# buck_boost.net
KiCad netlist of a schematic drawn in Altium Designer
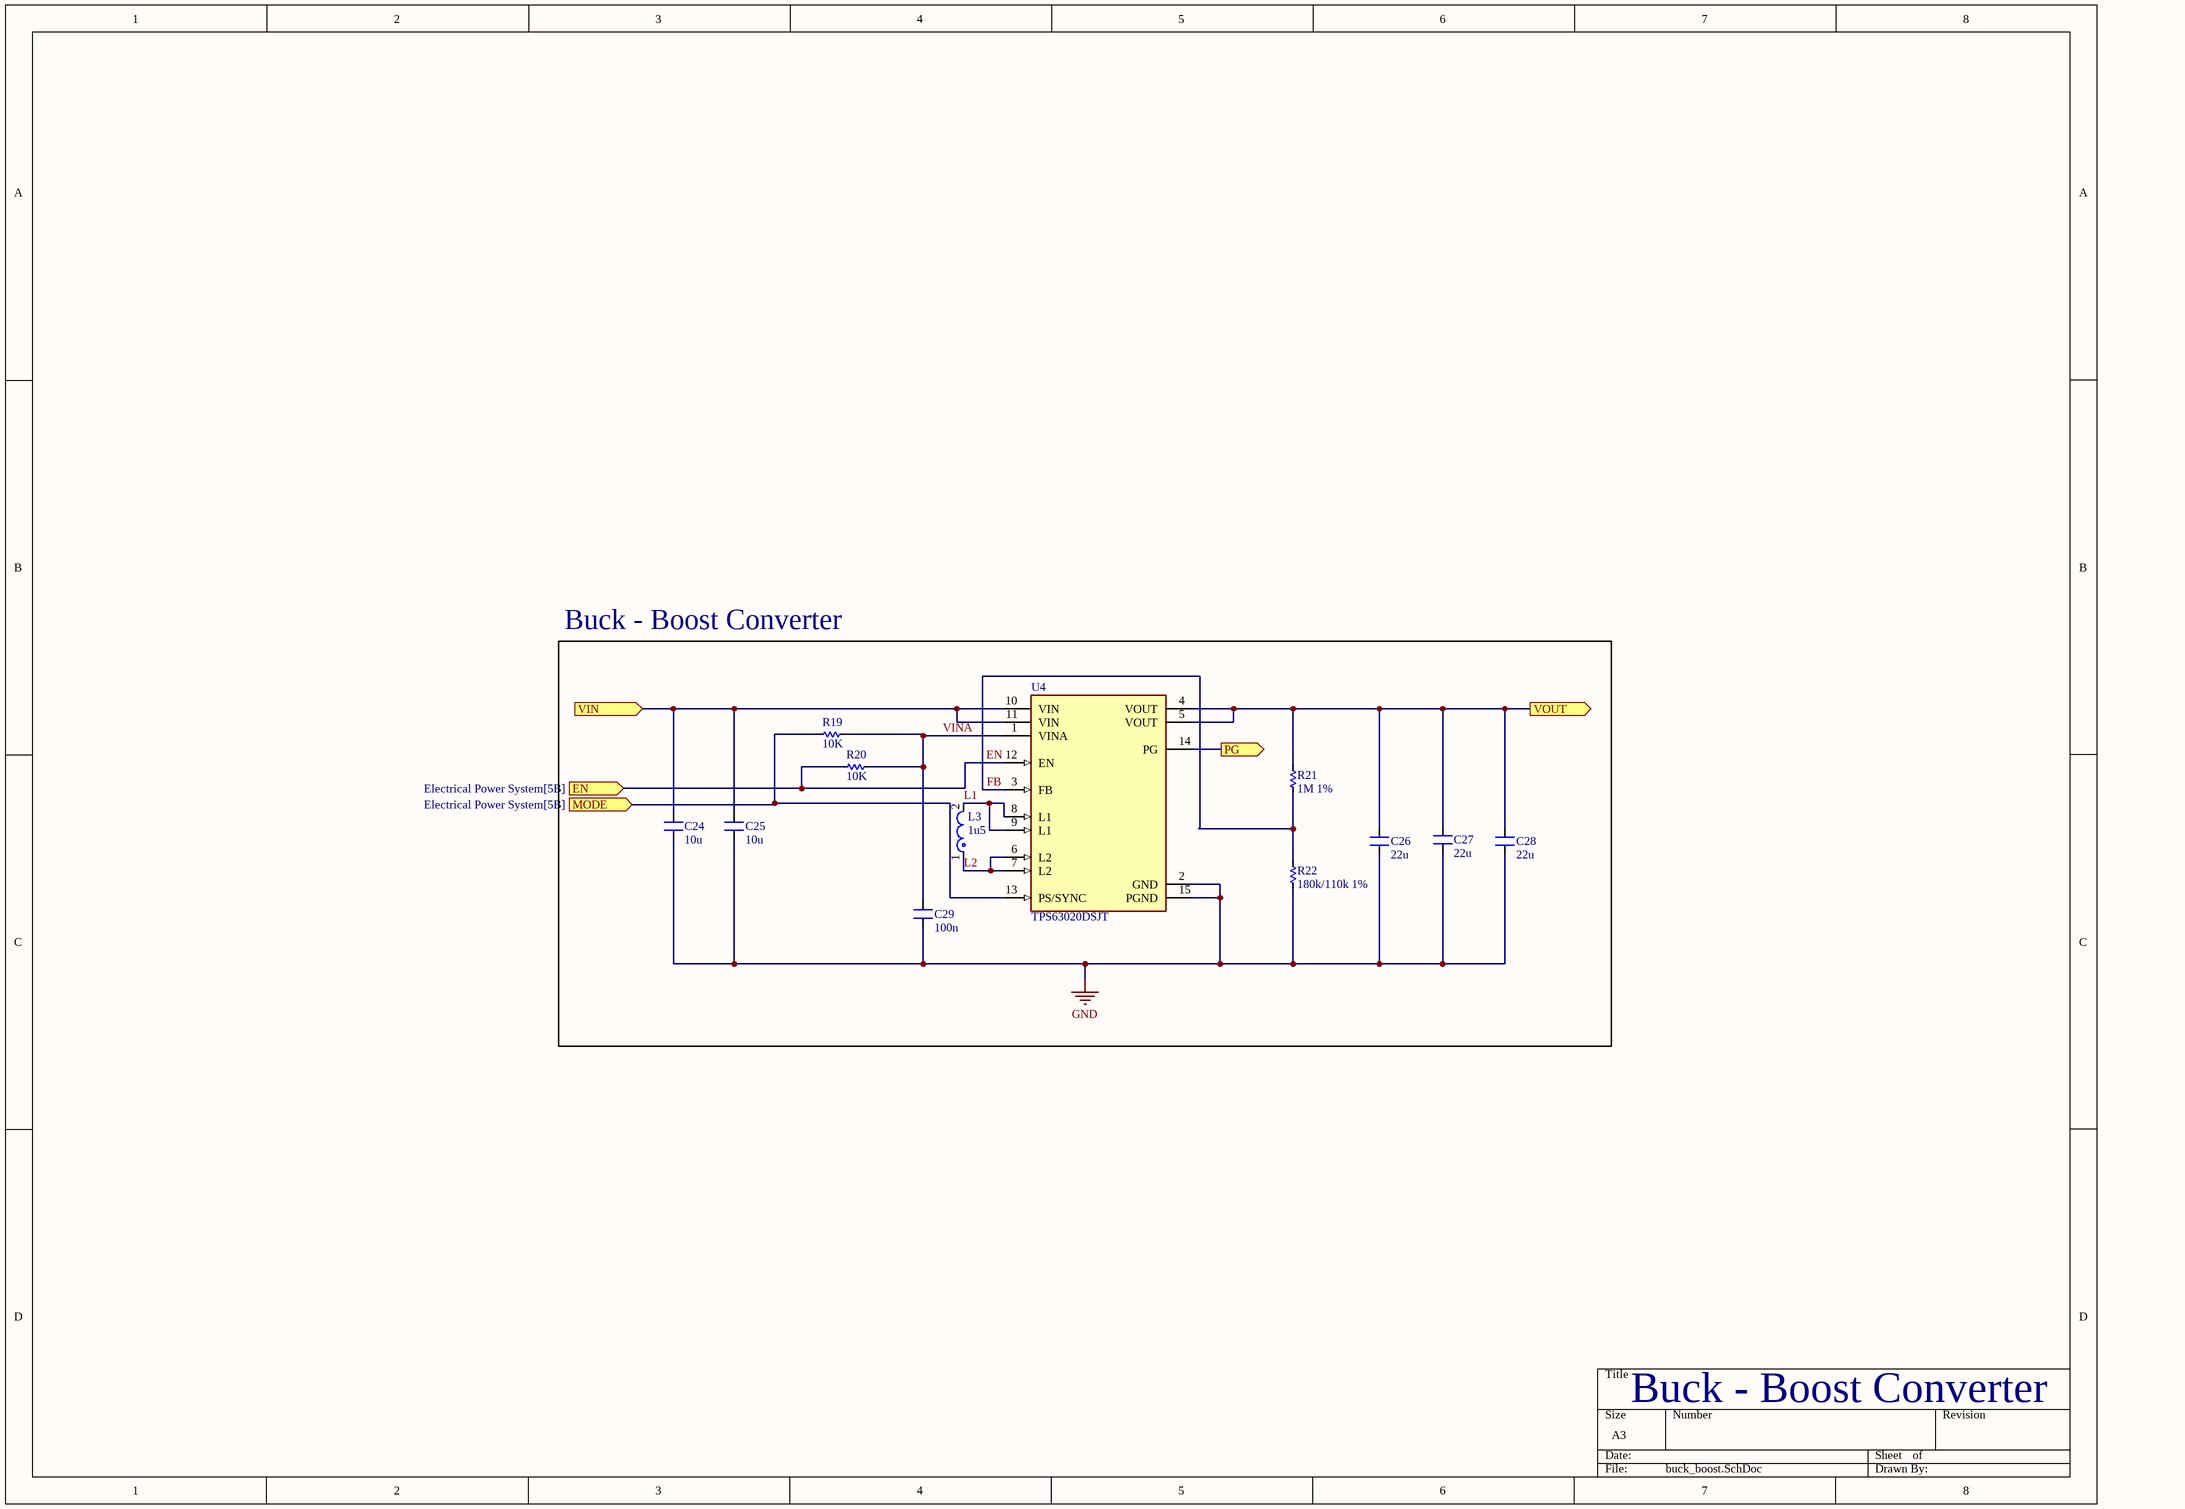
[diagram p0: buck_boost.SchDoc]

(export (version "E")
  (design (tool "Eeschema 10.0.6"))
  (components
    (comp (ref "C24")
      (value "10u")
      (footprint "CN-SMD-0603")
      (libsource (lib "Sang_library") (part "Capacitors"))
    )
    (comp (ref "C25")
      (value "10u")
      (footprint "CN-SMD-0603")
      (libsource (lib "Sang_library") (part "Capacitors"))
    )
    (comp (ref "C26")
      (value "22u")
      (footprint "CN-SMD-0603")
      (libsource (lib "Sang_library") (part "Capacitors"))
    )
    (comp (ref "C27")
      (value "22u")
      (footprint "CN-SMD-0603")
      (libsource (lib "Sang_library") (part "Capacitors"))
    )
    (comp (ref "C28")
      (value "22u")
      (footprint "CN-SMD-0603")
      (libsource (lib "Sang_library") (part "Capacitors"))
    )
    (comp (ref "C29")
      (value "100n")
      (footprint "CN-SMD-0603")
      (libsource (lib "Sang_library") (part "Capacitors"))
    )
    (comp (ref "L3")
      (value "1u5")
      (footprint "FP-XFL4020-MFG")
      (fields (field (name "TOLERANCE") "20%"))
      (libsource (lib "Altium Content Vault") (part "4cc4b267dca4c8e51f7102f422741d8"))
    )
    (comp (ref "R19")
      (value "10K")
      (footprint "RES-SMD-0805")
      (description "SMD")
      (fields
        (field (name "MANUFACTURER") "Generic Components")
        (field (name "PUBLISHER") "Altium Hobart Technology Centre")
      )
      (libsource (lib "Sang_library") (part "Res SMD"))
    )
    (comp (ref "R20")
      (value "10K")
      (footprint "RES-SMD-0805")
      (description "SMD")
      (fields
        (field (name "MANUFACTURER") "Generic Components")
        (field (name "PUBLISHER") "Altium Hobart Technology Centre")
      )
      (libsource (lib "Sang_library") (part "Res SMD"))
    )
    (comp (ref "R21")
      (value "1M 1%")
      (footprint "RES-SMD-0805")
      (description "SMD")
      (fields
        (field (name "MANUFACTURER") "Generic Components")
        (field (name "PUBLISHER") "Altium Hobart Technology Centre")
      )
      (libsource (lib "Sang_library") (part "Res SMD"))
    )
    (comp (ref "R22")
      (value "180k/110k 1%")
      (footprint "RES-SMD-0805")
      (description "SMD")
      (fields
        (field (name "MANUFACTURER") "Generic Components")
        (field (name "PUBLISHER") "Altium Hobart Technology Centre")
      )
      (libsource (lib "Sang_library") (part "Res SMD"))
    )
    (comp (ref "U4")
      (value "TPS63020DSJT")
      (footprint "FP-DSJ0014A-MFG")
      (description "IC REG BCK BST ADJ 3.5A 14VSON")
      (fields
        (field (name "MANUFACTURER") "Texas Instruments")
        (field (name "OCTOPART") "https://octopart.com/tps63020dsjt-texas+instruments-12976119")
      )
      (libsource (lib "Altium Content Vault") (part "ca84f4b88d1e031d86a58c77b9c066d"))
    )
  )
  (nets
    (net (code "1") (name "/EN") (class "Default")
      (node (ref "R20") (pin "2") (pinfunction "2_2") (pintype "passive"))
      (node (ref "U4") (pin "12") (pinfunction "EN_12") (pintype "input"))
    )
    (net (code "2") (name "/FB") (class "Default")
      (node (ref "R21") (pin "2") (pinfunction "2_2") (pintype "passive"))
      (node (ref "R22") (pin "1") (pinfunction "1_1") (pintype "passive"))
      (node (ref "U4") (pin "3") (pinfunction "FB_3") (pintype "input"))
    )
    (net (code "3") (name "/L1") (class "Default")
      (node (ref "L3") (pin "2") (pinfunction "2_2") (pintype "passive"))
      (node (ref "U4") (pin "8") (pinfunction "L1_8") (pintype "input"))
      (node (ref "U4") (pin "9") (pinfunction "L1_9") (pintype "input"))
    )
    (net (code "4") (name "/L2") (class "Default")
      (node (ref "L3") (pin "1") (pinfunction "1_1") (pintype "passive"))
      (node (ref "U4") (pin "6") (pinfunction "L2_6") (pintype "input"))
      (node (ref "U4") (pin "7") (pinfunction "L2_7") (pintype "input"))
    )
    (net (code "5") (name "/MODE") (class "Default")
      (node (ref "R19") (pin "2") (pinfunction "2_2") (pintype "passive"))
      (node (ref "U4") (pin "13") (pinfunction "PS/SYNC_13") (pintype "input"))
    )
    (net (code "6") (name "/PG") (class "Default")
      (node (ref "U4") (pin "14") (pinfunction "PG_14") (pintype "open_collector"))
    )
    (net (code "7") (name "/VIN") (class "Default")
      (node (ref "C24") (pin "2") (pinfunction "2_2") (pintype "passive"))
      (node (ref "C25") (pin "2") (pinfunction "2_2") (pintype "passive"))
      (node (ref "U4") (pin "10") (pinfunction "VIN_10") (pintype "power_in"))
      (node (ref "U4") (pin "11") (pinfunction "VIN_11") (pintype "power_in"))
    )
    (net (code "8") (name "/VINA") (class "Default")
      (node (ref "C29") (pin "2") (pinfunction "2_2") (pintype "passive"))
      (node (ref "R19") (pin "1") (pinfunction "1_1") (pintype "passive"))
      (node (ref "R20") (pin "1") (pinfunction "1_1") (pintype "passive"))
      (node (ref "U4") (pin "1") (pinfunction "VINA_1") (pintype "power_in"))
    )
    (net (code "9") (name "/VOUT") (class "Default")
      (node (ref "C26") (pin "2") (pinfunction "2_2") (pintype "passive"))
      (node (ref "C27") (pin "2") (pinfunction "2_2") (pintype "passive"))
      (node (ref "C28") (pin "2") (pinfunction "2_2") (pintype "passive"))
      (node (ref "R21") (pin "1") (pinfunction "1_1") (pintype "passive"))
      (node (ref "U4") (pin "4") (pinfunction "VOUT_4") (pintype "power_in"))
      (node (ref "U4") (pin "5") (pinfunction "VOUT_5") (pintype "power_in"))
    )
    (net (code "10") (name "GND") (class "Default")
      (node (ref "C24") (pin "1") (pinfunction "1_1") (pintype "passive"))
      (node (ref "C25") (pin "1") (pinfunction "1_1") (pintype "passive"))
      (node (ref "C26") (pin "1") (pinfunction "1_1") (pintype "passive"))
      (node (ref "C27") (pin "1") (pinfunction "1_1") (pintype "passive"))
      (node (ref "C28") (pin "1") (pinfunction "1_1") (pintype "passive"))
      (node (ref "C29") (pin "1") (pinfunction "1_1") (pintype "passive"))
      (node (ref "R22") (pin "2") (pinfunction "2_2") (pintype "passive"))
      (node (ref "U4") (pin "15") (pinfunction "PGND_15") (pintype "power_in"))
      (node (ref "U4") (pin "2") (pinfunction "GND_2") (pintype "power_in"))
    )
  )
)
